# LP_ECG_ECG-X02.net
KiCad netlist of a schematic drawn in Altium Designer
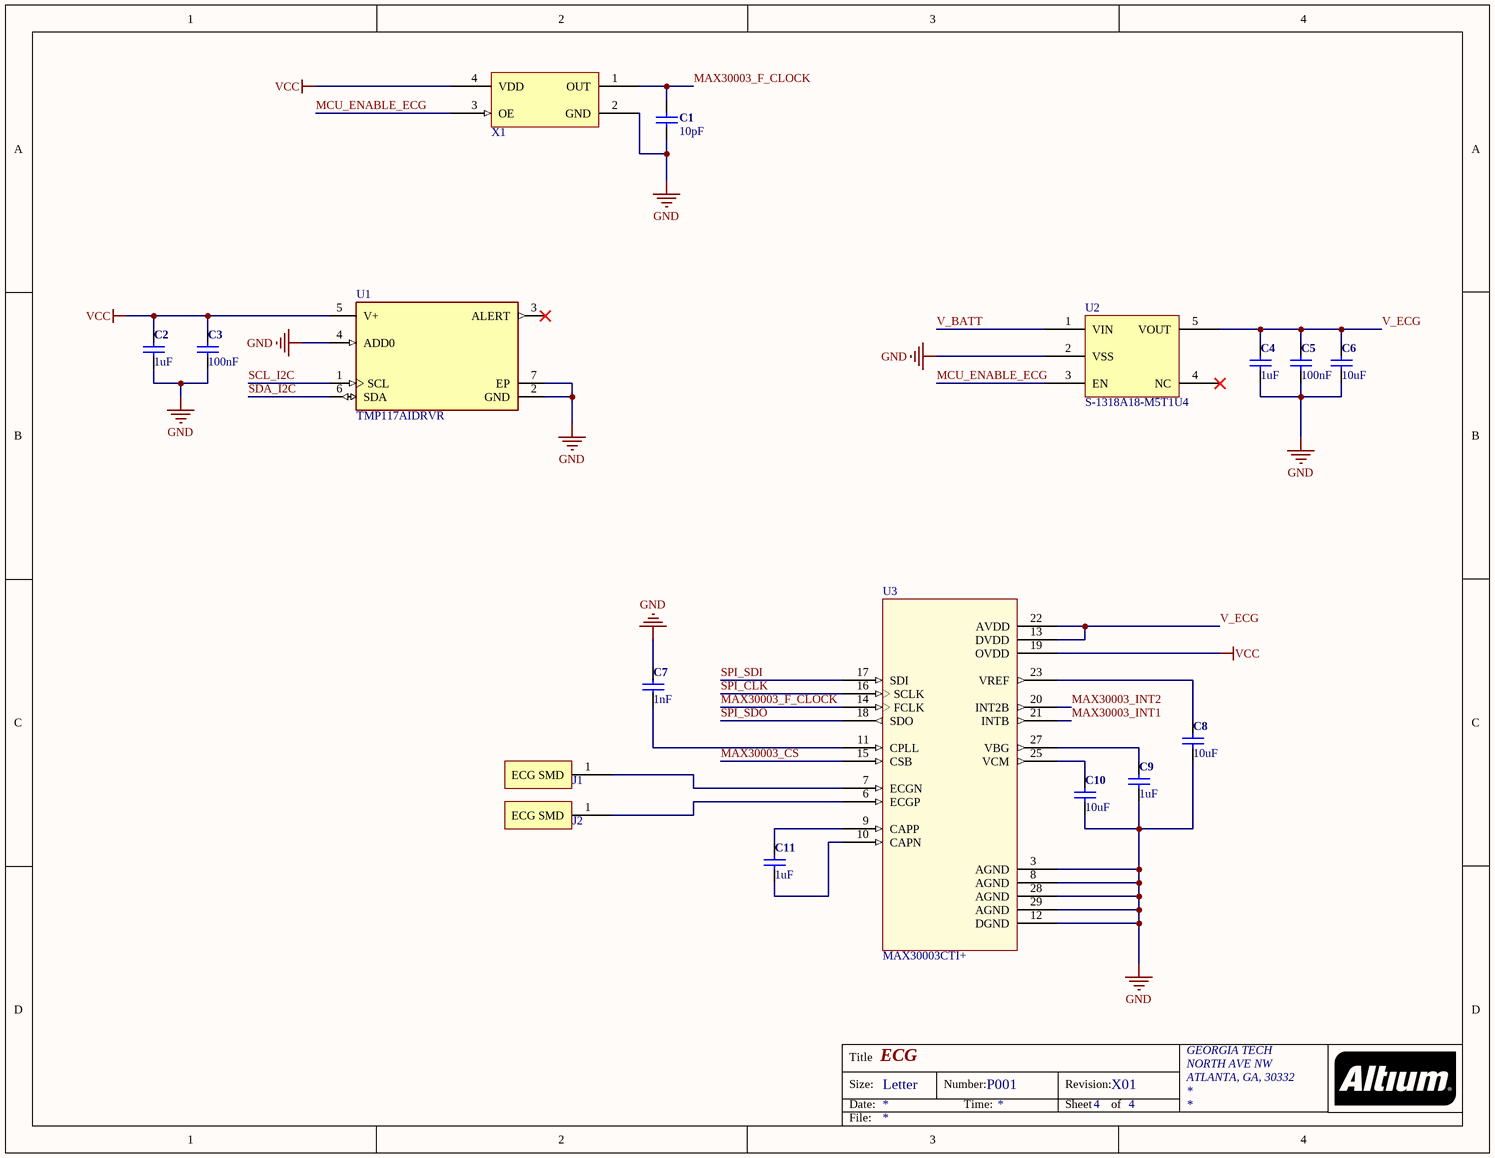
[diagram p0: LP_ECG_ECG-X02.SchDoc]

(export (version "E")
  (design (tool "Eeschema 10.0.6"))
  (components
    (comp (ref "C1")
      (value "10pF")
      (footprint "C0402")
      (fields
        (field (name "MANUFACTURER") "Murata")
        (field (name "MANUFACTURER PART NUMBER") "GJM1555C1H100JB01D")
      )
      (libsource (lib "LP_ECG-X01") (part "C-0402(1005)"))
    )
    (comp (ref "C2")
      (value "1uF")
      (footprint "C0402")
      (fields
        (field (name "MANUFACTURER") "Yageo")
        (field (name "MANUFACTURER PART NUMBER") "CC0402MRX5R5BB105")
        (field (name "TOLERANCE") "20%")
      )
      (libsource (lib "LP_ECG-X01") (part "C-0402(1005)"))
    )
    (comp (ref "C3")
      (value "100nF")
      (footprint "C0402")
      (fields
        (field (name "MANUFACTURER") "Taiyo Yuden")
        (field (name "MANUFACTURER PART NUMBER") "TMK105BJ104KV-F")
        (field (name "TOLERANCE") "10%")
      )
      (libsource (lib "LP_ECG-X01") (part "C-0402(1005)"))
    )
    (comp (ref "C4")
      (value "1uF")
      (footprint "C0402")
      (fields
        (field (name "MANUFACTURER") "Yageo")
        (field (name "MANUFACTURER PART NUMBER") "CC0402MRX5R5BB105")
        (field (name "TOLERANCE") "20%")
      )
      (libsource (lib "LP_ECG-X01") (part "C-0402(1005)"))
    )
    (comp (ref "C5")
      (value "100nF")
      (footprint "C0402")
      (fields
        (field (name "MANUFACTURER") "Taiyo Yuden")
        (field (name "MANUFACTURER PART NUMBER") "TMK105BJ104KV-F")
        (field (name "TOLERANCE") "10%")
      )
      (libsource (lib "LP_ECG-X01") (part "C-0402(1005)"))
    )
    (comp (ref "C6")
      (value "10uF")
      (footprint "C0402")
      (fields
        (field (name "MANUFACTURER") "Kyocera AVX")
        (field (name "MANUFACTURER PART NUMBER") "0402ZD106MAT2A")
      )
      (libsource (lib "LP_ECG-X01") (part "C-0402(1005)"))
    )
    (comp (ref "C7")
      (value "1nF")
      (footprint "C0402")
      (description "Ceramic Capacitor, Multilayer, Ceramic, 10V, 5% +Tol, 5% -Tol, C0G, -/+30ppm/Cel TC, 0.001uF, 0402")
      (fields
        (field (name "MANUFACTURER") "KEMET")
        (field (name "MANUFACTURER PART NUMBER") "C0402C102J8GAC7867")
      )
      (libsource (lib "LP_ECG-X01") (part "C-0402(1005)"))
    )
    (comp (ref "C8")
      (value "10uF")
      (footprint "C0402")
      (fields
        (field (name "MANUFACTURER") "Kyocera AVX")
        (field (name "MANUFACTURER PART NUMBER") "0402ZD106MAT2A")
      )
      (libsource (lib "LP_ECG-X01") (part "C-0402(1005)"))
    )
    (comp (ref "C9")
      (value "1uF")
      (footprint "C0402")
      (fields
        (field (name "MANUFACTURER") "Yageo")
        (field (name "MANUFACTURER PART NUMBER") "CC0402MRX5R5BB105")
        (field (name "TOLERANCE") "20%")
      )
      (libsource (lib "LP_ECG-X01") (part "C-0402(1005)"))
    )
    (comp (ref "C10")
      (value "10uF")
      (footprint "C0402")
      (fields
        (field (name "MANUFACTURER") "Kyocera AVX")
        (field (name "MANUFACTURER PART NUMBER") "0402ZD106MAT2A")
      )
      (libsource (lib "LP_ECG-X01") (part "C-0402(1005)"))
    )
    (comp (ref "C11")
      (value "1uF")
      (footprint "C0402")
      (fields
        (field (name "MANUFACTURER") "Yageo")
        (field (name "MANUFACTURER PART NUMBER") "CC0402MRX5R5BB105")
        (field (name "TOLERANCE") "20%")
      )
      (libsource (lib "LP_ECG-X01") (part "C-0402(1005)"))
    )
    (comp (ref "J1")
      (value "ECG_SMD_CONNECTOR")
      (footprint "ecg_connector")
      (description "SMD CONNECTOR FOR ECG")
      (libsource (lib "LP_ECG-X01") (part "ECG_SMD_CONNECTOR"))
    )
    (comp (ref "J2")
      (value "ECG_SMD_CONNECTOR")
      (footprint "ecg_connector")
      (description "SMD CONNECTOR FOR ECG")
      (libsource (lib "LP_ECG-X01") (part "ECG_SMD_CONNECTOR"))
    )
    (comp (ref "U1")
      (value "TMP117AIDRVR")
      (footprint "TMP117AIDRVR")
      (description "TEMPERATURE SENSOR")
      (fields
        (field (name "OCTOPART") "https://octopart.com/tmp117aidrvr-texas+instruments-95511044")
        (field (name "MANUFACTURER") "Texas Instruments")
      )
      (libsource (lib "LP_ECG-X01") (part "bceab6869a9cb85cf5675529ee35ce4"))
    )
    (comp (ref "U2")
      (value "S-1318A18-M5T1U4")
      (footprint "SOT-23-5")
      (description "Fixed Positive LDO Regulator")
      (fields (field (name "MANUFACTURER") "ABLIC"))
      (libsource (lib "LP_ECG-X02") (part "S-1318A18-M5T1U4"))
    )
    (comp (ref "U3")
      (value "MAX30003CTI+")
      (footprint "QFN50P500X500X80-29N")
      (description "Analog Circuit, 1 Func, CMOS")
      (fields (field (name "MANUFACTURER") "Maxim"))
      (libsource (lib "LP_ECG-X01") (part "MAX30003CTI+"))
    )
    (comp (ref "X1")
      (value "OSCILLATOR-32.768KHZ")
      (footprint "OM-7605-C8-32.768KHZ")
      (description "Osc Xo 32.768KHZ SMD")
      (fields
        (field (name "MANUFACTURER") "Micro Crystal")
        (field (name "MANUFACTURER PART NUMBER") "OM-7605-C8-32.768KHZ-20PPM-TA-QC")
      )
      (libsource (lib "LP_ECG-X02") (part "OM-7605-C8-32.768KHZ"))
    )
  )
  (nets
    (net (code "1") (name "/MAX30003_CS") (class "Default")
      (node (ref "U3") (pin "15") (pinfunction "CSB_15") (pintype "input"))
    )
    (net (code "2") (name "/MAX30003_F_CLOCK") (class "Default")
      (node (ref "C1") (pin "1") (pinfunction "1_1") (pintype "passive"))
      (node (ref "U3") (pin "14") (pinfunction "FCLK_14") (pintype "input"))
      (node (ref "X1") (pin "1") (pinfunction "OUT_1") (pintype "passive"))
    )
    (net (code "3") (name "/MAX30003_INT1") (class "Default")
      (node (ref "U3") (pin "21") (pinfunction "INTB_21") (pintype "output"))
    )
    (net (code "4") (name "/MAX30003_INT2") (class "Default")
      (node (ref "U3") (pin "20") (pinfunction "INT2B_20") (pintype "output"))
    )
    (net (code "5") (name "/MCU_ENABLE_ECG") (class "Default")
      (node (ref "U2") (pin "3") (pinfunction "EN_3") (pintype "passive"))
      (node (ref "X1") (pin "3") (pinfunction "OE_3") (pintype "input"))
    )
    (net (code "6") (name "/SCL_I2C") (class "Default")
      (node (ref "U1") (pin "1") (pinfunction "SCL_1") (pintype "input"))
    )
    (net (code "7") (name "/SDA_I2C") (class "Default")
      (node (ref "U1") (pin "6") (pinfunction "SDA_6") (pintype "bidirectional"))
    )
    (net (code "8") (name "/SPI_CLK") (class "Default")
      (node (ref "U3") (pin "16") (pinfunction "SCLK_16") (pintype "input"))
    )
    (net (code "9") (name "/SPI_SDI") (class "Default")
      (node (ref "U3") (pin "17") (pinfunction "SDI_17") (pintype "input"))
    )
    (net (code "10") (name "/SPI_SDO") (class "Default")
      (node (ref "U3") (pin "18") (pinfunction "SDO_18") (pintype "output"))
    )
    (net (code "11") (name "/V_BATT") (class "Default")
      (node (ref "U2") (pin "1") (pinfunction "VIN_1") (pintype "passive"))
    )
    (net (code "12") (name "/V_ECG") (class "Default")
      (node (ref "C4") (pin "1") (pinfunction "1_1") (pintype "passive"))
      (node (ref "C5") (pin "2") (pinfunction "2_2") (pintype "passive"))
      (node (ref "C6") (pin "1") (pinfunction "1_1") (pintype "passive"))
      (node (ref "U2") (pin "5") (pinfunction "VOUT_5") (pintype "passive"))
      (node (ref "U3") (pin "13") (pinfunction "DVDD_13") (pintype "power_in"))
      (node (ref "U3") (pin "22") (pinfunction "AVDD_22") (pintype "power_in"))
    )
    (net (code "13") (name "GND") (class "Default")
      (node (ref "C1") (pin "2") (pinfunction "2_2") (pintype "passive"))
      (node (ref "C10") (pin "2") (pinfunction "2_2") (pintype "passive"))
      (node (ref "C2") (pin "2") (pinfunction "2_2") (pintype "passive"))
      (node (ref "C3") (pin "1") (pinfunction "1_1") (pintype "passive"))
      (node (ref "C4") (pin "2") (pinfunction "2_2") (pintype "passive"))
      (node (ref "C5") (pin "1") (pinfunction "1_1") (pintype "passive"))
      (node (ref "C6") (pin "2") (pinfunction "2_2") (pintype "passive"))
      (node (ref "C7") (pin "1") (pinfunction "1_1") (pintype "passive"))
      (node (ref "C8") (pin "2") (pinfunction "2_2") (pintype "passive"))
      (node (ref "C9") (pin "2") (pinfunction "2_2") (pintype "passive"))
      (node (ref "U1") (pin "2") (pinfunction "GND_2") (pintype "power_in"))
      (node (ref "U1") (pin "4") (pinfunction "ADD0_4") (pintype "input"))
      (node (ref "U1") (pin "7") (pinfunction "EP_7") (pintype "passive"))
      (node (ref "U2") (pin "2") (pinfunction "VSS_2") (pintype "passive"))
      (node (ref "U3") (pin "12") (pinfunction "DGND_12") (pintype "power_in"))
      (node (ref "U3") (pin "28") (pinfunction "AGND_28") (pintype "power_in"))
      (node (ref "U3") (pin "29") (pinfunction "AGND_29") (pintype "power_in"))
      (node (ref "U3") (pin "3") (pinfunction "AGND_3") (pintype "power_in"))
      (node (ref "U3") (pin "8") (pinfunction "AGND_8") (pintype "power_in"))
      (node (ref "X1") (pin "2") (pinfunction "GND_2") (pintype "power_in"))
    )
    (net (code "14") (name "Net-(J1-ECG_SMD)") (class "Default")
      (node (ref "J1") (pin "1") (pinfunction "ECG_SMD_1") (pintype "passive"))
      (node (ref "U3") (pin "7") (pinfunction "ECGN_7") (pintype "input"))
    )
    (net (code "15") (name "Net-(J2-ECG_SMD)") (class "Default")
      (node (ref "J2") (pin "1") (pinfunction "ECG_SMD_1") (pintype "passive"))
      (node (ref "U3") (pin "6") (pinfunction "ECGP_6") (pintype "input"))
    )
    (net (code "16") (name "Net-(U3-CAPN)") (class "Default")
      (node (ref "C11") (pin "2") (pinfunction "2_2") (pintype "passive"))
      (node (ref "U3") (pin "10") (pinfunction "CAPN_10") (pintype "input"))
    )
    (net (code "17") (name "Net-(U3-CAPP)") (class "Default")
      (node (ref "C11") (pin "1") (pinfunction "1_1") (pintype "passive"))
      (node (ref "U3") (pin "9") (pinfunction "CAPP_9") (pintype "input"))
    )
    (net (code "18") (name "Net-(U3-CPLL)") (class "Default")
      (node (ref "C7") (pin "2") (pinfunction "2_2") (pintype "passive"))
      (node (ref "U3") (pin "11") (pinfunction "CPLL_11") (pintype "input"))
    )
    (net (code "19") (name "Net-(U3-VBG)") (class "Default")
      (node (ref "C9") (pin "1") (pinfunction "1_1") (pintype "passive"))
      (node (ref "U3") (pin "27") (pinfunction "VBG_27") (pintype "output"))
    )
    (net (code "20") (name "Net-(U3-VCM)") (class "Default")
      (node (ref "C10") (pin "1") (pinfunction "1_1") (pintype "passive"))
      (node (ref "U3") (pin "25") (pinfunction "VCM_25") (pintype "output"))
    )
    (net (code "21") (name "Net-(U3-VREF)") (class "Default")
      (node (ref "C8") (pin "1") (pinfunction "1_1") (pintype "passive"))
      (node (ref "U3") (pin "23") (pinfunction "VREF_23") (pintype "output"))
    )
    (net (code "22") (name "VCC") (class "Default")
      (node (ref "C2") (pin "1") (pinfunction "1_1") (pintype "passive"))
      (node (ref "C3") (pin "2") (pinfunction "2_2") (pintype "passive"))
      (node (ref "U1") (pin "5") (pinfunction "V+_5") (pintype "power_in"))
      (node (ref "U3") (pin "19") (pinfunction "OVDD_19") (pintype "power_in"))
      (node (ref "X1") (pin "4") (pinfunction "VDD_4") (pintype "power_in"))
    )
    (net (code "23") (name "unconnected-(U1-ALERT-Pad3)") (class "Default")
      (node (ref "U1") (pin "3") (pinfunction "ALERT_3") (pintype "output+no_connect"))
    )
    (net (code "24") (name "unconnected-(U2-NC-Pad4)") (class "Default")
      (node (ref "U2") (pin "4") (pinfunction "NC_4") (pintype "passive+no_connect"))
    )
  )
)
